# skithSTMv2.net
KiCad netlist of a schematic drawn in EAGLE
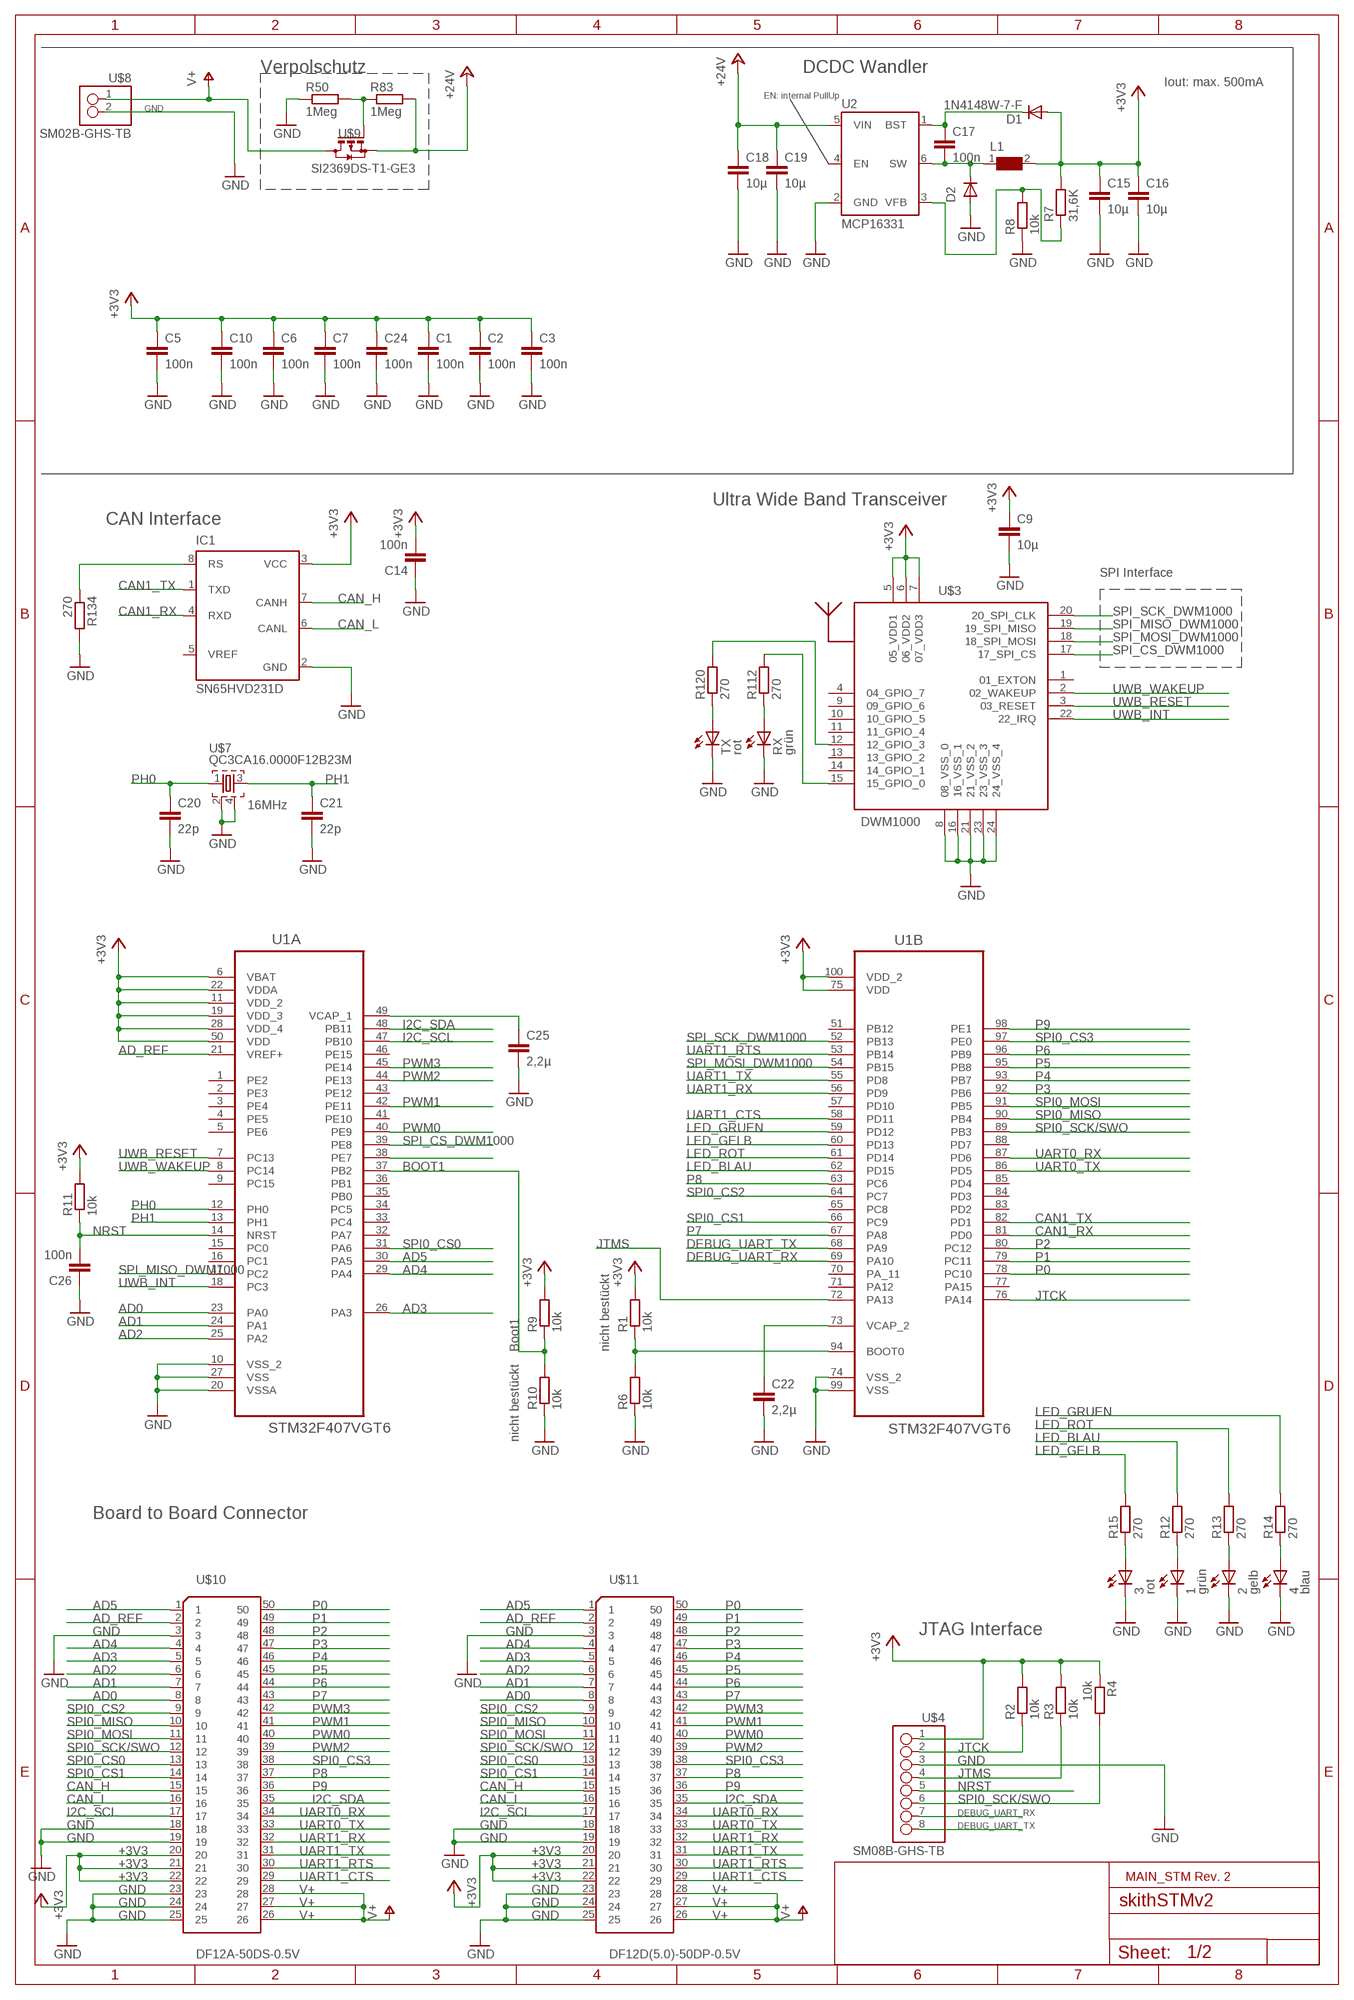
[diagram p0: schematic, sheet 1]
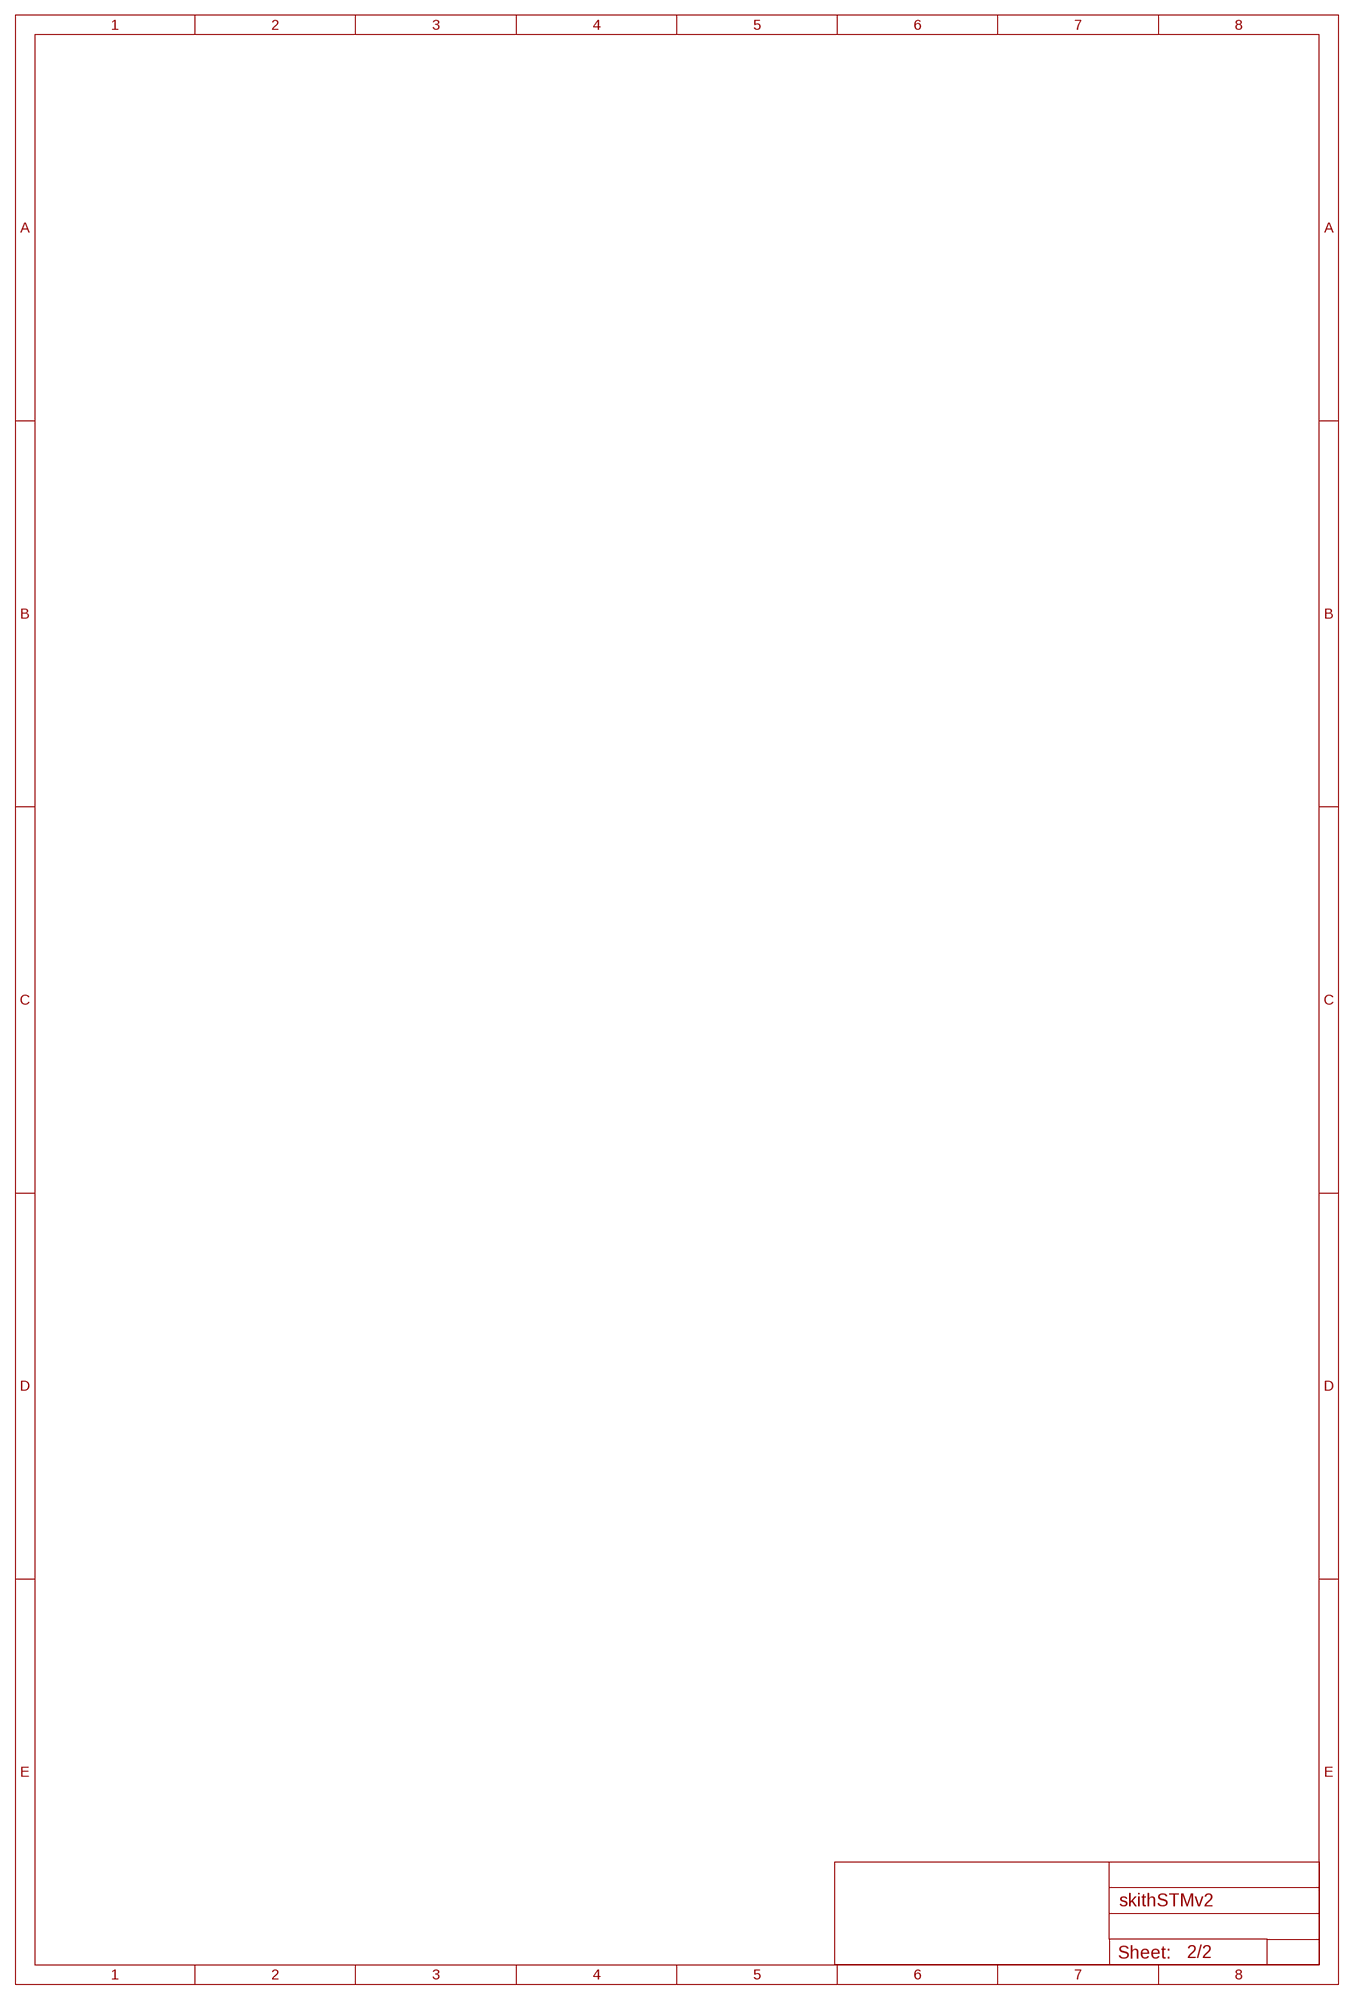
[diagram p1: schematic, sheet 2]

(export (version "E")
  (design (tool "Eeschema 10.0.6"))
  (components
    (comp (ref "1")
      (value "grün")
      (footprint "eagle-import:SML0603")
      (libsource (lib "eagle-import") (part "LEDSML0603"))
    )
    (comp (ref "2")
      (value "gelb")
      (footprint "eagle-import:SML0603")
      (libsource (lib "eagle-import") (part "LEDSML0603"))
    )
    (comp (ref "3")
      (value "rot")
      (footprint "eagle-import:SML0603")
      (libsource (lib "eagle-import") (part "LEDSML0603"))
    )
    (comp (ref "4")
      (value "blau")
      (footprint "eagle-import:SML0603")
      (libsource (lib "eagle-import") (part "LEDSML0603"))
    )
    (comp (ref "C1")
      (value "100n")
      (footprint "eagle-import:C0402")
      (libsource (lib "eagle-import") (part "C-EUC0402"))
    )
    (comp (ref "C2")
      (value "100n")
      (footprint "eagle-import:C0402")
      (libsource (lib "eagle-import") (part "C-EUC0402"))
    )
    (comp (ref "C3")
      (value "100n")
      (footprint "eagle-import:C0402")
      (libsource (lib "eagle-import") (part "C-EUC0402"))
    )
    (comp (ref "C5")
      (value "100n")
      (footprint "eagle-import:C0402")
      (libsource (lib "eagle-import") (part "C-EUC0402"))
    )
    (comp (ref "C6")
      (value "100n")
      (footprint "eagle-import:C0402")
      (libsource (lib "eagle-import") (part "C-EUC0402"))
    )
    (comp (ref "C7")
      (value "100n")
      (footprint "eagle-import:C0402")
      (libsource (lib "eagle-import") (part "C-EUC0402"))
    )
    (comp (ref "C9")
      (value "10µ")
      (footprint "eagle-import:C0805")
      (libsource (lib "eagle-import") (part "C-EUC0805"))
    )
    (comp (ref "C10")
      (value "100n")
      (footprint "eagle-import:C0402")
      (libsource (lib "eagle-import") (part "C-EUC0402"))
    )
    (comp (ref "C14")
      (value "100n")
      (footprint "eagle-import:C0402")
      (libsource (lib "eagle-import") (part "C-EUC0402"))
    )
    (comp (ref "C15")
      (value "10µ")
      (footprint "eagle-import:C0805")
      (libsource (lib "eagle-import") (part "C-EUC0805"))
    )
    (comp (ref "C16")
      (value "10µ")
      (footprint "eagle-import:C0805")
      (libsource (lib "eagle-import") (part "C-EUC0805"))
    )
    (comp (ref "C17")
      (value "100n")
      (footprint "eagle-import:C0402")
      (libsource (lib "eagle-import") (part "C-EUC0402"))
    )
    (comp (ref "C18")
      (value "10µ")
      (footprint "eagle-import:C0805")
      (libsource (lib "eagle-import") (part "C-EUC0805"))
    )
    (comp (ref "C19")
      (value "10µ")
      (footprint "eagle-import:C0805")
      (libsource (lib "eagle-import") (part "C-EUC0805"))
    )
    (comp (ref "C20")
      (value "22p")
      (footprint "eagle-import:C0402")
      (libsource (lib "eagle-import") (part "C-EUC0402"))
    )
    (comp (ref "C21")
      (value "22p")
      (footprint "eagle-import:C0402")
      (libsource (lib "eagle-import") (part "C-EUC0402"))
    )
    (comp (ref "C22")
      (value "2,2µ")
      (footprint "eagle-import:C0402")
      (libsource (lib "eagle-import") (part "C-EUC0402"))
    )
    (comp (ref "C24")
      (value "100n")
      (footprint "eagle-import:C0402")
      (libsource (lib "eagle-import") (part "C-EUC0402"))
    )
    (comp (ref "C25")
      (value "2,2µ")
      (footprint "eagle-import:C0402")
      (libsource (lib "eagle-import") (part "C-EUC0402"))
    )
    (comp (ref "C26")
      (value "100n")
      (footprint "eagle-import:C0402")
      (libsource (lib "eagle-import") (part "C-EUC0402"))
    )
    (comp (ref "D1")
      (value "1N4148W-7-F")
      (footprint "eagle-import:SOD123")
      (libsource (lib "eagle-import") (part "DIODE-SOD123"))
    )
    (comp (ref "D2")
      (value "DIODE-DO214AC")
      (footprint "eagle-import:DO214AC")
      (libsource (lib "eagle-import") (part "DIODE-DO214AC"))
    )
    (comp (ref "IC1")
      (value "SN65HVD231D")
      (footprint "eagle-import:SO8")
      (libsource (lib "eagle-import") (part "PCA82C250T"))
    )
    (comp (ref "L1")
      (value "WE-TPC-744025150_2828")
      (footprint "eagle-import:WE-TPC_2828")
      (fields (field (name "MPN") "744025150"))
      (libsource (lib "eagle-import") (part "WE-TPC_2828-744025150"))
    )
    (comp (ref "R1")
      (value "10k")
      (footprint "eagle-import:R0402")
      (libsource (lib "eagle-import") (part "R-EU_R0402"))
    )
    (comp (ref "R2")
      (value "10k")
      (footprint "eagle-import:R0402")
      (libsource (lib "eagle-import") (part "R-EU_R0402"))
    )
    (comp (ref "R3")
      (value "10k")
      (footprint "eagle-import:R0402")
      (libsource (lib "eagle-import") (part "R-EU_R0402"))
    )
    (comp (ref "R4")
      (value "10k")
      (footprint "eagle-import:R0402")
      (libsource (lib "eagle-import") (part "R-EU_R0402"))
    )
    (comp (ref "R6")
      (value "10k")
      (footprint "eagle-import:R0402")
      (libsource (lib "eagle-import") (part "R-EU_R0402"))
    )
    (comp (ref "R7")
      (value "31,6K")
      (footprint "eagle-import:R0402")
      (libsource (lib "eagle-import") (part "R-EU_R0402"))
    )
    (comp (ref "R8")
      (value "10k")
      (footprint "eagle-import:R0402")
      (libsource (lib "eagle-import") (part "R-EU_R0402"))
    )
    (comp (ref "R9")
      (value "10k")
      (footprint "eagle-import:R0402")
      (libsource (lib "eagle-import") (part "R-EU_R0402"))
    )
    (comp (ref "R10")
      (value "10k")
      (footprint "eagle-import:R0402")
      (libsource (lib "eagle-import") (part "R-EU_R0402"))
    )
    (comp (ref "R11")
      (value "10k")
      (footprint "eagle-import:R0402")
      (libsource (lib "eagle-import") (part "R-EU_R0402"))
    )
    (comp (ref "R12")
      (value "270")
      (footprint "eagle-import:R0402")
      (libsource (lib "eagle-import") (part "R-EU_R0402"))
    )
    (comp (ref "R13")
      (value "270")
      (footprint "eagle-import:R0402")
      (libsource (lib "eagle-import") (part "R-EU_R0402"))
    )
    (comp (ref "R14")
      (value "270")
      (footprint "eagle-import:R0402")
      (libsource (lib "eagle-import") (part "R-EU_R0402"))
    )
    (comp (ref "R15")
      (value "270")
      (footprint "eagle-import:R0402")
      (libsource (lib "eagle-import") (part "R-EU_R0402"))
    )
    (comp (ref "R50")
      (value "1Meg")
      (footprint "eagle-import:R0402")
      (libsource (lib "eagle-import") (part "R-EU_R0402"))
    )
    (comp (ref "R83")
      (value "1Meg")
      (footprint "eagle-import:R0402")
      (libsource (lib "eagle-import") (part "R-EU_R0402"))
    )
    (comp (ref "R112")
      (value "270")
      (footprint "eagle-import:R0402")
      (libsource (lib "eagle-import") (part "R-EU_R0402"))
    )
    (comp (ref "R120")
      (value "270")
      (footprint "eagle-import:R0402")
      (libsource (lib "eagle-import") (part "R-EU_R0402"))
    )
    (comp (ref "R134")
      (value "270")
      (footprint "eagle-import:R0402")
      (libsource (lib "eagle-import") (part "R-EU_R0402"))
    )
    (comp (ref "RX")
      (value "grün")
      (footprint "eagle-import:SML0603")
      (libsource (lib "eagle-import") (part "LEDSML0603"))
    )
    (comp (ref "TX")
      (value "rot")
      (footprint "eagle-import:SML0603")
      (libsource (lib "eagle-import") (part "LEDSML0603"))
    )
    (comp (ref "U$3")
      (value "DWM1000")
      (footprint "eagle-import:DWM1000")
      (libsource (lib "eagle-import") (part "DWM1000"))
    )
    (comp (ref "U$4")
      (value "SM08B-GHS-TB")
      (footprint "eagle-import:SM08B-GHS-TB")
      (libsource (lib "eagle-import") (part "SM08B-GHS-TB"))
    )
    (comp (ref "U$7")
      (value "QC3CA16.0000F12B23M")
      (footprint "eagle-import:LFXTAL055998")
      (libsource (lib "eagle-import") (part "QC3CA12.0000F12B23M"))
    )
    (comp (ref "U$8")
      (value "SM02B-GHS-TB")
      (footprint "eagle-import:SM02B-GHS-TB")
      (libsource (lib "eagle-import") (part "SM02B-GHS-TB"))
    )
    (comp (ref "U$9")
      (value "SI2369DS-T1-GE3")
      (footprint "eagle-import:SOT23")
      (libsource (lib "eagle-import") (part "SI2369DS-T1-GE3"))
    )
    (comp (ref "U$10")
      (value "DF12A-50DS-0.5V")
      (footprint "eagle-import:DF12A-50DS-0.5V")
      (libsource (lib "eagle-import") (part "DF12A-50DS-0.5V"))
    )
    (comp (ref "U$11")
      (value "DF12D(5.0)-50DP-0.5V")
      (footprint "eagle-import:DF12D(5.0)-50DP-0.5V")
      (libsource (lib "eagle-import") (part "DF12D(5.0)-50DP-0.5V"))
    )
    (comp (ref "U1")
      (value "STM32F407VGT6")
      (footprint "eagle-import:QFP50P1600X1600X160-100N")
      (libsource (lib "eagle-import") (part "STM32F407VGT6"))
    )
    (comp (ref "U2")
      (value "MCP16331")
      (footprint "eagle-import:SOT23-6")
      (libsource (lib "eagle-import") (part "MCP16331"))
    )
  )
  (nets
    (net (code "1") (name "+3V3") (class "Default")
      (node (ref "C1") (pin "1") (pinfunction "1_1") (pintype "passive"))
      (node (ref "C10") (pin "1") (pinfunction "1_1") (pintype "passive"))
      (node (ref "C14") (pin "2") (pinfunction "2_2") (pintype "passive"))
      (node (ref "C15") (pin "1") (pinfunction "1_1") (pintype "passive"))
      (node (ref "C16") (pin "1") (pinfunction "1_1") (pintype "passive"))
      (node (ref "C2") (pin "1") (pinfunction "1_1") (pintype "passive"))
      (node (ref "C24") (pin "1") (pinfunction "1_1") (pintype "passive"))
      (node (ref "C3") (pin "1") (pinfunction "1_1") (pintype "passive"))
      (node (ref "C5") (pin "1") (pinfunction "1_1") (pintype "passive"))
      (node (ref "C6") (pin "1") (pinfunction "1_1") (pintype "passive"))
      (node (ref "C7") (pin "1") (pinfunction "1_1") (pintype "passive"))
      (node (ref "C9") (pin "1") (pinfunction "1_1") (pintype "passive"))
      (node (ref "D1") (pin "A") (pinfunction "A_A") (pintype "passive"))
      (node (ref "IC1") (pin "3") (pinfunction "VCC_3") (pintype "power_in"))
      (node (ref "L1") (pin "2") (pinfunction "2_2") (pintype "passive"))
      (node (ref "R1") (pin "2") (pinfunction "2_2") (pintype "passive"))
      (node (ref "R11") (pin "2") (pinfunction "2_2") (pintype "passive"))
      (node (ref "R2") (pin "2") (pinfunction "2_2") (pintype "passive"))
      (node (ref "R3") (pin "2") (pinfunction "2_2") (pintype "passive"))
      (node (ref "R4") (pin "1") (pinfunction "1_1") (pintype "passive"))
      (node (ref "R7") (pin "2") (pinfunction "2_2") (pintype "passive"))
      (node (ref "R9") (pin "2") (pinfunction "2_2") (pintype "passive"))
      (node (ref "U$10") (pin "20") (pinfunction "20_20") (pintype "bidirectional"))
      (node (ref "U$10") (pin "21") (pinfunction "21_21") (pintype "bidirectional"))
      (node (ref "U$10") (pin "22") (pinfunction "22_22") (pintype "bidirectional"))
      (node (ref "U$11") (pin "20") (pinfunction "20_20") (pintype "bidirectional"))
      (node (ref "U$11") (pin "21") (pinfunction "21_21") (pintype "bidirectional"))
      (node (ref "U$11") (pin "22") (pinfunction "22_22") (pintype "bidirectional"))
      (node (ref "U$3") (pin "5") (pinfunction "05_VDD1_5") (pintype "bidirectional"))
      (node (ref "U$3") (pin "6") (pinfunction "06_VDD2_6") (pintype "bidirectional"))
      (node (ref "U$3") (pin "7") (pinfunction "07_VDD3_7") (pintype "bidirectional"))
      (node (ref "U$4") (pin "1") (pinfunction "P$1_1") (pintype "bidirectional"))
      (node (ref "U1") (pin "100") (pinfunction "VDD_2_100") (pintype "power_in"))
      (node (ref "U1") (pin "11") (pinfunction "VDD_2_11") (pintype "power_in"))
      (node (ref "U1") (pin "19") (pinfunction "VDD_3_19") (pintype "power_in"))
      (node (ref "U1") (pin "22") (pinfunction "VDDA_22") (pintype "power_in"))
      (node (ref "U1") (pin "28") (pinfunction "VDD_4_28") (pintype "power_in"))
      (node (ref "U1") (pin "50") (pinfunction "VDD_50") (pintype "power_in"))
      (node (ref "U1") (pin "6") (pinfunction "VBAT_6") (pintype "power_in"))
      (node (ref "U1") (pin "75") (pinfunction "VDD_75") (pintype "power_in"))
    )
    (net (code "2") (name "+24V") (class "Default")
      (node (ref "C18") (pin "1") (pinfunction "1_1") (pintype "passive"))
      (node (ref "C19") (pin "1") (pinfunction "1_1") (pintype "passive"))
      (node (ref "R83") (pin "2") (pinfunction "2_2") (pintype "passive"))
      (node (ref "U$9") (pin "2") (pinfunction "S_2") (pintype "passive"))
      (node (ref "U2") (pin "5") (pinfunction "VIN_5") (pintype "bidirectional"))
    )
    (net (code "3") (name "AD0") (class "Default")
      (node (ref "U$10") (pin "8") (pinfunction "8_8") (pintype "bidirectional"))
      (node (ref "U$11") (pin "8") (pinfunction "8_8") (pintype "bidirectional"))
      (node (ref "U1") (pin "23") (pinfunction "PA0_23") (pintype "bidirectional"))
    )
    (net (code "4") (name "AD1") (class "Default")
      (node (ref "U$10") (pin "7") (pinfunction "7_7") (pintype "bidirectional"))
      (node (ref "U$11") (pin "7") (pinfunction "7_7") (pintype "bidirectional"))
      (node (ref "U1") (pin "24") (pinfunction "PA1_24") (pintype "bidirectional"))
    )
    (net (code "5") (name "AD2") (class "Default")
      (node (ref "U$10") (pin "6") (pinfunction "6_6") (pintype "bidirectional"))
      (node (ref "U$11") (pin "6") (pinfunction "6_6") (pintype "bidirectional"))
      (node (ref "U1") (pin "25") (pinfunction "PA2_25") (pintype "bidirectional"))
    )
    (net (code "6") (name "AD3") (class "Default")
      (node (ref "U$10") (pin "5") (pinfunction "5_5") (pintype "bidirectional"))
      (node (ref "U$11") (pin "5") (pinfunction "5_5") (pintype "bidirectional"))
      (node (ref "U1") (pin "26") (pinfunction "PA3_26") (pintype "bidirectional"))
    )
    (net (code "7") (name "AD4") (class "Default")
      (node (ref "U$10") (pin "4") (pinfunction "4_4") (pintype "bidirectional"))
      (node (ref "U$11") (pin "4") (pinfunction "4_4") (pintype "bidirectional"))
      (node (ref "U1") (pin "29") (pinfunction "PA4_29") (pintype "bidirectional"))
    )
    (net (code "8") (name "AD5") (class "Default")
      (node (ref "U$10") (pin "1") (pinfunction "1_1") (pintype "bidirectional"))
      (node (ref "U$11") (pin "1") (pinfunction "1_1") (pintype "bidirectional"))
      (node (ref "U1") (pin "30") (pinfunction "PA5_30") (pintype "bidirectional"))
    )
    (net (code "9") (name "AD_REF") (class "Default")
      (node (ref "U$10") (pin "2") (pinfunction "2_2") (pintype "bidirectional"))
      (node (ref "U$11") (pin "2") (pinfunction "2_2") (pintype "bidirectional"))
      (node (ref "U1") (pin "21") (pinfunction "VREF+_21") (pintype "power_in"))
    )
    (net (code "10") (name "BOOT1") (class "Default")
      (node (ref "R10") (pin "2") (pinfunction "2_2") (pintype "passive"))
      (node (ref "R9") (pin "1") (pinfunction "1_1") (pintype "passive"))
      (node (ref "U1") (pin "37") (pinfunction "PB2_37") (pintype "bidirectional"))
    )
    (net (code "11") (name "CAN1_RX") (class "Default")
      (node (ref "IC1") (pin "4") (pinfunction "RXD_4") (pintype "output"))
      (node (ref "U1") (pin "81") (pinfunction "PD0_81") (pintype "bidirectional"))
    )
    (net (code "12") (name "CAN1_TX") (class "Default")
      (node (ref "IC1") (pin "1") (pinfunction "TXD_1") (pintype "input"))
      (node (ref "U1") (pin "82") (pinfunction "PD1_82") (pintype "bidirectional"))
    )
    (net (code "13") (name "CAN_H") (class "Default")
      (node (ref "IC1") (pin "7") (pinfunction "CANH_7") (pintype "bidirectional"))
      (node (ref "U$10") (pin "15") (pinfunction "15_15") (pintype "bidirectional"))
      (node (ref "U$11") (pin "15") (pinfunction "15_15") (pintype "bidirectional"))
    )
    (net (code "14") (name "CAN_L") (class "Default")
      (node (ref "IC1") (pin "6") (pinfunction "CANL_6") (pintype "bidirectional"))
      (node (ref "U$10") (pin "16") (pinfunction "16_16") (pintype "bidirectional"))
      (node (ref "U$11") (pin "16") (pinfunction "16_16") (pintype "bidirectional"))
    )
    (net (code "15") (name "DEBUG_UART_RX") (class "Default")
      (node (ref "U$4") (pin "7") (pinfunction "P$7_7") (pintype "bidirectional"))
      (node (ref "U1") (pin "69") (pinfunction "PA10_69") (pintype "bidirectional"))
    )
    (net (code "16") (name "DEBUG_UART_TX") (class "Default")
      (node (ref "U$4") (pin "8") (pinfunction "P$8_8") (pintype "bidirectional"))
      (node (ref "U1") (pin "68") (pinfunction "PA9_68") (pintype "bidirectional"))
    )
    (net (code "17") (name "GND") (class "Default")
      (node (ref "1") (pin "C") (pinfunction "C_C") (pintype "passive"))
      (node (ref "2") (pin "C") (pinfunction "C_C") (pintype "passive"))
      (node (ref "3") (pin "C") (pinfunction "C_C") (pintype "passive"))
      (node (ref "4") (pin "C") (pinfunction "C_C") (pintype "passive"))
      (node (ref "C1") (pin "2") (pinfunction "2_2") (pintype "passive"))
      (node (ref "C10") (pin "2") (pinfunction "2_2") (pintype "passive"))
      (node (ref "C14") (pin "1") (pinfunction "1_1") (pintype "passive"))
      (node (ref "C15") (pin "2") (pinfunction "2_2") (pintype "passive"))
      (node (ref "C16") (pin "2") (pinfunction "2_2") (pintype "passive"))
      (node (ref "C18") (pin "2") (pinfunction "2_2") (pintype "passive"))
      (node (ref "C19") (pin "2") (pinfunction "2_2") (pintype "passive"))
      (node (ref "C2") (pin "2") (pinfunction "2_2") (pintype "passive"))
      (node (ref "C20") (pin "2") (pinfunction "2_2") (pintype "passive"))
      (node (ref "C21") (pin "2") (pinfunction "2_2") (pintype "passive"))
      (node (ref "C22") (pin "2") (pinfunction "2_2") (pintype "passive"))
      (node (ref "C24") (pin "2") (pinfunction "2_2") (pintype "passive"))
      (node (ref "C25") (pin "2") (pinfunction "2_2") (pintype "passive"))
      (node (ref "C26") (pin "1") (pinfunction "1_1") (pintype "passive"))
      (node (ref "C3") (pin "2") (pinfunction "2_2") (pintype "passive"))
      (node (ref "C5") (pin "2") (pinfunction "2_2") (pintype "passive"))
      (node (ref "C6") (pin "2") (pinfunction "2_2") (pintype "passive"))
      (node (ref "C7") (pin "2") (pinfunction "2_2") (pintype "passive"))
      (node (ref "C9") (pin "2") (pinfunction "2_2") (pintype "passive"))
      (node (ref "D2") (pin "A") (pinfunction "A_A") (pintype "passive"))
      (node (ref "IC1") (pin "2") (pinfunction "GND_2") (pintype "power_in"))
      (node (ref "R10") (pin "1") (pinfunction "1_1") (pintype "passive"))
      (node (ref "R134") (pin "2") (pinfunction "2_2") (pintype "passive"))
      (node (ref "R50") (pin "1") (pinfunction "1_1") (pintype "passive"))
      (node (ref "R6") (pin "1") (pinfunction "1_1") (pintype "passive"))
      (node (ref "R8") (pin "1") (pinfunction "1_1") (pintype "passive"))
      (node (ref "RX") (pin "C") (pinfunction "C_C") (pintype "passive"))
      (node (ref "TX") (pin "C") (pinfunction "C_C") (pintype "passive"))
      (node (ref "U$10") (pin "18") (pinfunction "18_18") (pintype "bidirectional"))
      (node (ref "U$10") (pin "19") (pinfunction "19_19") (pintype "bidirectional"))
      (node (ref "U$10") (pin "23") (pinfunction "23_23") (pintype "bidirectional"))
      (node (ref "U$10") (pin "24") (pinfunction "24_24") (pintype "bidirectional"))
      (node (ref "U$10") (pin "25") (pinfunction "25_25") (pintype "bidirectional"))
      (node (ref "U$10") (pin "3") (pinfunction "3_3") (pintype "bidirectional"))
      (node (ref "U$11") (pin "18") (pinfunction "18_18") (pintype "bidirectional"))
      (node (ref "U$11") (pin "19") (pinfunction "19_19") (pintype "bidirectional"))
      (node (ref "U$11") (pin "23") (pinfunction "23_23") (pintype "bidirectional"))
      (node (ref "U$11") (pin "24") (pinfunction "24_24") (pintype "bidirectional"))
      (node (ref "U$11") (pin "25") (pinfunction "25_25") (pintype "bidirectional"))
      (node (ref "U$11") (pin "3") (pinfunction "3_3") (pintype "bidirectional"))
      (node (ref "U$3") (pin "16") (pinfunction "16_VSS_1_16") (pintype "bidirectional"))
      (node (ref "U$3") (pin "21") (pinfunction "21_VSS_2_21") (pintype "bidirectional"))
      (node (ref "U$3") (pin "23") (pinfunction "23_VSS_3_23") (pintype "bidirectional"))
      (node (ref "U$3") (pin "24") (pinfunction "24_VSS_4_24") (pintype "bidirectional"))
      (node (ref "U$3") (pin "8") (pinfunction "08_VSS_0_8") (pintype "bidirectional"))
      (node (ref "U$4") (pin "3") (pinfunction "P$3_3") (pintype "bidirectional"))
      (node (ref "U$7") (pin "2") (pinfunction "2_2") (pintype "passive"))
      (node (ref "U$7") (pin "4") (pinfunction "4_4") (pintype "passive"))
      (node (ref "U$8") (pin "2") (pinfunction "P$2_2") (pintype "bidirectional"))
      (node (ref "U1") (pin "10") (pinfunction "VSS_2_10") (pintype "passive"))
      (node (ref "U1") (pin "20") (pinfunction "VSSA_20") (pintype "passive"))
      (node (ref "U1") (pin "27") (pinfunction "VSS_27") (pintype "passive"))
      (node (ref "U1") (pin "74") (pinfunction "VSS_2_74") (pintype "passive"))
      (node (ref "U1") (pin "99") (pinfunction "VSS_99") (pintype "passive"))
      (node (ref "U2") (pin "2") (pinfunction "GND_2") (pintype "bidirectional"))
    )
    (net (code "18") (name "I2C_SCL") (class "Default")
      (node (ref "U$10") (pin "17") (pinfunction "17_17") (pintype "bidirectional"))
      (node (ref "U$11") (pin "17") (pinfunction "17_17") (pintype "bidirectional"))
      (node (ref "U1") (pin "47") (pinfunction "PB10_47") (pintype "bidirectional"))
    )
    (net (code "19") (name "I2C_SDA") (class "Default")
      (node (ref "U$10") (pin "35") (pinfunction "35_35") (pintype "bidirectional"))
      (node (ref "U$11") (pin "35") (pinfunction "35_35") (pintype "bidirectional"))
      (node (ref "U1") (pin "48") (pinfunction "PB11_48") (pintype "bidirectional"))
    )
    (net (code "20") (name "JTCK") (class "Default")
      (node (ref "R2") (pin "1") (pinfunction "1_1") (pintype "passive"))
      (node (ref "U$4") (pin "2") (pinfunction "P$2_2") (pintype "bidirectional"))
      (node (ref "U1") (pin "76") (pinfunction "PA14_76") (pintype "bidirectional"))
    )
    (net (code "21") (name "JTMS") (class "Default")
      (node (ref "R3") (pin "1") (pinfunction "1_1") (pintype "passive"))
      (node (ref "U$4") (pin "4") (pinfunction "P$4_4") (pintype "bidirectional"))
      (node (ref "U1") (pin "72") (pinfunction "PA13_72") (pintype "bidirectional"))
    )
    (net (code "22") (name "LED_BLAU") (class "Default")
      (node (ref "R12") (pin "2") (pinfunction "2_2") (pintype "passive"))
      (node (ref "U1") (pin "62") (pinfunction "PD15_62") (pintype "bidirectional"))
    )
    (net (code "23") (name "LED_GELB") (class "Default")
      (node (ref "R15") (pin "2") (pinfunction "2_2") (pintype "passive"))
      (node (ref "U1") (pin "60") (pinfunction "PD13_60") (pintype "bidirectional"))
    )
    (net (code "24") (name "LED_GRUEN") (class "Default")
      (node (ref "R14") (pin "2") (pinfunction "2_2") (pintype "passive"))
      (node (ref "U1") (pin "59") (pinfunction "PD12_59") (pintype "bidirectional"))
    )
    (net (code "25") (name "LED_ROT") (class "Default")
      (node (ref "R13") (pin "2") (pinfunction "2_2") (pintype "passive"))
      (node (ref "U1") (pin "61") (pinfunction "PD14_61") (pintype "bidirectional"))
    )
    (net (code "26") (name "NRST") (class "Default")
      (node (ref "C26") (pin "2") (pinfunction "2_2") (pintype "passive"))
      (node (ref "R11") (pin "1") (pinfunction "1_1") (pintype "passive"))
      (node (ref "U$4") (pin "5") (pinfunction "P$5_5") (pintype "bidirectional"))
      (node (ref "U1") (pin "14") (pinfunction "NRST_14") (pintype "bidirectional"))
    )
    (net (code "27") (name "Net-(1-PadA)") (class "Default")
      (node (ref "1") (pin "A") (pinfunction "A_A") (pintype "passive"))
      (node (ref "R12") (pin "1") (pinfunction "1_1") (pintype "passive"))
    )
    (net (code "28") (name "Net-(2-PadA)") (class "Default")
      (node (ref "2") (pin "A") (pinfunction "A_A") (pintype "passive"))
      (node (ref "R13") (pin "1") (pinfunction "1_1") (pintype "passive"))
    )
    (net (code "29") (name "Net-(3-PadA)") (class "Default")
      (node (ref "3") (pin "A") (pinfunction "A_A") (pintype "passive"))
      (node (ref "R15") (pin "1") (pinfunction "1_1") (pintype "passive"))
    )
    (net (code "30") (name "Net-(4-PadA)") (class "Default")
      (node (ref "4") (pin "A") (pinfunction "A_A") (pintype "passive"))
      (node (ref "R14") (pin "1") (pinfunction "1_1") (pintype "passive"))
    )
    (net (code "31") (name "Net-(IC1-RS)") (class "Default")
      (node (ref "IC1") (pin "8") (pinfunction "RS_8") (pintype "input"))
      (node (ref "R134") (pin "1") (pinfunction "1_1") (pintype "passive"))
    )
    (net (code "32") (name "Net-(R112-Pad1)") (class "Default")
      (node (ref "R112") (pin "1") (pinfunction "1_1") (pintype "passive"))
      (node (ref "RX") (pin "A") (pinfunction "A_A") (pintype "passive"))
    )
    (net (code "33") (name "Net-(R120-Pad1)") (class "Default")
      (node (ref "R120") (pin "1") (pinfunction "1_1") (pintype "passive"))
      (node (ref "TX") (pin "A") (pinfunction "A_A") (pintype "passive"))
    )
    (net (code "34") (name "Net-(U$3-12_GPIO_3)") (class "Default")
      (node (ref "R120") (pin "2") (pinfunction "2_2") (pintype "passive"))
      (node (ref "U$3") (pin "12") (pinfunction "12_GPIO_3_12") (pintype "bidirectional"))
    )
    (net (code "35") (name "Net-(U$3-15_GPIO_0)") (class "Default")
      (node (ref "R112") (pin "2") (pinfunction "2_2") (pintype "passive"))
      (node (ref "U$3") (pin "15") (pinfunction "15_GPIO_0_15") (pintype "bidirectional"))
    )
    (net (code "36") (name "Net-(U$9-G)") (class "Default")
      (node (ref "R50") (pin "2") (pinfunction "2_2") (pintype "passive"))
      (node (ref "R83") (pin "1") (pinfunction "1_1") (pintype "passive"))
      (node (ref "U$9") (pin "1") (pinfunction "G_1") (pintype "passive"))
    )
    (net (code "37") (name "Net-(U1A-VCAP_1)") (class "Default")
      (node (ref "C25") (pin "1") (pinfunction "1_1") (pintype "passive"))
      (node (ref "U1") (pin "49") (pinfunction "VCAP_1_49") (pintype "power_in"))
    )
    (net (code "38") (name "Net-(U1B-BOOT0)") (class "Default")
      (node (ref "R1") (pin "1") (pinfunction "1_1") (pintype "passive"))
      (node (ref "R6") (pin "2") (pinfunction "2_2") (pintype "passive"))
      (node (ref "U1") (pin "94") (pinfunction "BOOT0_94") (pintype "input"))
    )
    (net (code "39") (name "Net-(U1B-VCAP_2)") (class "Default")
      (node (ref "C22") (pin "1") (pinfunction "1_1") (pintype "passive"))
      (node (ref "U1") (pin "73") (pinfunction "VCAP_2_73") (pintype "power_in"))
    )
    (net (code "40") (name "Net-(U2-BST)") (class "Default")
      (node (ref "C17") (pin "1") (pinfunction "1_1") (pintype "passive"))
      (node (ref "D1") (pin "C") (pinfunction "C_C") (pintype "passive"))
      (node (ref "U2") (pin "1") (pinfunction "BST_1") (pintype "bidirectional"))
    )
    (net (code "41") (name "Net-(U2-SW)") (class "Default")
      (node (ref "C17") (pin "2") (pinfunction "2_2") (pintype "passive"))
      (node (ref "D2") (pin "C") (pinfunction "C_C") (pintype "passive"))
      (node (ref "L1") (pin "1") (pinfunction "1_1") (pintype "passive"))
      (node (ref "U2") (pin "6") (pinfunction "SW_6") (pintype "bidirectional"))
    )
    (net (code "42") (name "Net-(U2-VFB)") (class "Default")
      (node (ref "R7") (pin "1") (pinfunction "1_1") (pintype "passive"))
      (node (ref "R8") (pin "2") (pinfunction "2_2") (pintype "passive"))
      (node (ref "U2") (pin "3") (pinfunction "VFB_3") (pintype "bidirectional"))
    )
    (net (code "43") (name "P0") (class "Default")
      (node (ref "U$10") (pin "50") (pinfunction "50_50") (pintype "bidirectional"))
      (node (ref "U$11") (pin "50") (pinfunction "50_50") (pintype "bidirectional"))
      (node (ref "U1") (pin "78") (pinfunction "PC10_78") (pintype "bidirectional"))
    )
    (net (code "44") (name "P1") (class "Default")
      (node (ref "U$10") (pin "49") (pinfunction "49_49") (pintype "bidirectional"))
      (node (ref "U$11") (pin "49") (pinfunction "49_49") (pintype "bidirectional"))
      (node (ref "U1") (pin "79") (pinfunction "PC11_79") (pintype "bidirectional"))
    )
    (net (code "45") (name "P2") (class "Default")
      (node (ref "U$10") (pin "48") (pinfunction "48_48") (pintype "bidirectional"))
      (node (ref "U$11") (pin "48") (pinfunction "48_48") (pintype "bidirectional"))
      (node (ref "U1") (pin "80") (pinfunction "PC12_80") (pintype "bidirectional"))
    )
    (net (code "46") (name "P3") (class "Default")
      (node (ref "U$10") (pin "47") (pinfunction "47_47") (pintype "bidirectional"))
      (node (ref "U$11") (pin "47") (pinfunction "47_47") (pintype "bidirectional"))
      (node (ref "U1") (pin "92") (pinfunction "PB6_92") (pintype "bidirectional"))
    )
    (net (code "47") (name "P4") (class "Default")
      (node (ref "U$10") (pin "46") (pinfunction "46_46") (pintype "bidirectional"))
      (node (ref "U$11") (pin "46") (pinfunction "46_46") (pintype "bidirectional"))
      (node (ref "U1") (pin "93") (pinfunction "PB7_93") (pintype "bidirectional"))
    )
    (net (code "48") (name "P5") (class "Default")
      (node (ref "U$10") (pin "45") (pinfunction "45_45") (pintype "bidirectional"))
      (node (ref "U$11") (pin "45") (pinfunction "45_45") (pintype "bidirectional"))
      (node (ref "U1") (pin "95") (pinfunction "PB8_95") (pintype "bidirectional"))
    )
    (net (code "49") (name "P6") (class "Default")
      (node (ref "U$10") (pin "44") (pinfunction "44_44") (pintype "bidirectional"))
      (node (ref "U$11") (pin "44") (pinfunction "44_44") (pintype "bidirectional"))
      (node (ref "U1") (pin "96") (pinfunction "PB9_96") (pintype "bidirectional"))
    )
    (net (code "50") (name "P7") (class "Default")
      (node (ref "U$10") (pin "43") (pinfunction "43_43") (pintype "bidirectional"))
      (node (ref "U$11") (pin "43") (pinfunction "43_43") (pintype "bidirectional"))
      (node (ref "U1") (pin "67") (pinfunction "PA8_67") (pintype "bidirectional"))
    )
    (net (code "51") (name "P8") (class "Default")
      (node (ref "U$10") (pin "37") (pinfunction "37_37") (pintype "bidirectional"))
      (node (ref "U$11") (pin "37") (pinfunction "37_37") (pintype "bidirectional"))
      (node (ref "U1") (pin "63") (pinfunction "PC6_63") (pintype "bidirectional"))
    )
    (net (code "52") (name "P9") (class "Default")
      (node (ref "U$10") (pin "36") (pinfunction "36_36") (pintype "bidirectional"))
      (node (ref "U$11") (pin "36") (pinfunction "36_36") (pintype "bidirectional"))
      (node (ref "U1") (pin "98") (pinfunction "PE1_98") (pintype "bidirectional"))
    )
    (net (code "53") (name "PH0") (class "Default")
      (node (ref "C20") (pin "1") (pinfunction "1_1") (pintype "passive"))
      (node (ref "U$7") (pin "1") (pinfunction "1_1") (pintype "passive"))
      (node (ref "U1") (pin "12") (pinfunction "PH0_12") (pintype "bidirectional"))
    )
    (net (code "54") (name "PH1") (class "Default")
      (node (ref "C21") (pin "1") (pinfunction "1_1") (pintype "passive"))
      (node (ref "U$7") (pin "3") (pinfunction "3_3") (pintype "passive"))
      (node (ref "U1") (pin "13") (pinfunction "PH1_13") (pintype "bidirectional"))
    )
    (net (code "55") (name "PWM0") (class "Default")
      (node (ref "U$10") (pin "40") (pinfunction "40_40") (pintype "bidirectional"))
      (node (ref "U$11") (pin "40") (pinfunction "40_40") (pintype "bidirectional"))
      (node (ref "U1") (pin "40") (pinfunction "PE9_40") (pintype "bidirectional"))
    )
    (net (code "56") (name "PWM1") (class "Default")
      (node (ref "U$10") (pin "41") (pinfunction "41_41") (pintype "bidirectional"))
      (node (ref "U$11") (pin "41") (pinfunction "41_41") (pintype "bidirectional"))
      (node (ref "U1") (pin "42") (pinfunction "PE11_42") (pintype "bidirectional"))
    )
    (net (code "57") (name "PWM2") (class "Default")
      (node (ref "U$10") (pin "39") (pinfunction "39_39") (pintype "bidirectional"))
      (node (ref "U$11") (pin "39") (pinfunction "39_39") (pintype "bidirectional"))
      (node (ref "U1") (pin "44") (pinfunction "PE13_44") (pintype "bidirectional"))
    )
    (net (code "58") (name "PWM3") (class "Default")
      (node (ref "U$10") (pin "42") (pinfunction "42_42") (pintype "bidirectional"))
      (node (ref "U$11") (pin "42") (pinfunction "42_42") (pintype "bidirectional"))
      (node (ref "U1") (pin "45") (pinfunction "PE14_45") (pintype "bidirectional"))
    )
    (net (code "59") (name "SPI0_CS0") (class "Default")
      (node (ref "U$10") (pin "13") (pinfunction "13_13") (pintype "bidirectional"))
      (node (ref "U$11") (pin "13") (pinfunction "13_13") (pintype "bidirectional"))
      (node (ref "U1") (pin "31") (pinfunction "PA6_31") (pintype "bidirectional"))
    )
    (net (code "60") (name "SPI0_CS1") (class "Default")
      (node (ref "U$10") (pin "14") (pinfunction "14_14") (pintype "bidirectional"))
      (node (ref "U$11") (pin "14") (pinfunction "14_14") (pintype "bidirectional"))
      (node (ref "U1") (pin "66") (pinfunction "PC9_66") (pintype "bidirectional"))
    )
    (net (code "61") (name "SPI0_CS2") (class "Default")
      (node (ref "U$10") (pin "9") (pinfunction "9_9") (pintype "bidirectional"))
      (node (ref "U$11") (pin "9") (pinfunction "9_9") (pintype "bidirectional"))
      (node (ref "U1") (pin "64") (pinfunction "PC7_64") (pintype "bidirectional"))
    )
    (net (code "62") (name "SPI0_CS3") (class "Default")
      (node (ref "U$10") (pin "38") (pinfunction "38_38") (pintype "bidirectional"))
      (node (ref "U$11") (pin "38") (pinfunction "38_38") (pintype "bidirectional"))
      (node (ref "U1") (pin "97") (pinfunction "PE0_97") (pintype "bidirectional"))
    )
    (net (code "63") (name "SPI0_MISO") (class "Default")
      (node (ref "U$10") (pin "10") (pinfunction "10_10") (pintype "bidirectional"))
      (node (ref "U$11") (pin "10") (pinfunction "10_10") (pintype "bidirectional"))
      (node (ref "U1") (pin "90") (pinfunction "PB4_90") (pintype "bidirectional"))
    )
    (net (code "64") (name "SPI0_MOSI") (class "Default")
      (node (ref "U$10") (pin "11") (pinfunction "11_11") (pintype "bidirectional"))
      (node (ref "U$11") (pin "11") (pinfunction "11_11") (pintype "bidirectional"))
      (node (ref "U1") (pin "91") (pinfunction "PB5_91") (pintype "bidirectional"))
    )
    (net (code "65") (name "SPI0_SCK{slash}SWO") (class "Default")
      (node (ref "R4") (pin "2") (pinfunction "2_2") (pintype "passive"))
      (node (ref "U$10") (pin "12") (pinfunction "12_12") (pintype "bidirectional"))
      (node (ref "U$11") (pin "12") (pinfunction "12_12") (pintype "bidirectional"))
      (node (ref "U$4") (pin "6") (pinfunction "P$6_6") (pintype "bidirectional"))
      (node (ref "U1") (pin "89") (pinfunction "PB3_89") (pintype "bidirectional"))
    )
    (net (code "66") (name "SPI_CS_DWM1000") (class "Default")
      (node (ref "U$3") (pin "17") (pinfunction "17_SPI_CS_17") (pintype "bidirectional"))
      (node (ref "U1") (pin "39") (pinfunction "PE8_39") (pintype "bidirectional"))
    )
    (net (code "67") (name "SPI_MISO_DWM1000") (class "Default")
      (node (ref "U$3") (pin "19") (pinfunction "19_SPI_MISO_19") (pintype "bidirectional"))
      (node (ref "U1") (pin "17") (pinfunction "PC2_17") (pintype "bidirectional"))
    )
    (net (code "68") (name "SPI_MOSI_DWM1000") (class "Default")
      (node (ref "U$3") (pin "18") (pinfunction "18_SPI_MOSI_18") (pintype "bidirectional"))
      (node (ref "U1") (pin "54") (pinfunction "PB15_54") (pintype "bidirectional"))
    )
    (net (code "69") (name "SPI_SCK_DWM1000") (class "Default")
      (node (ref "U$3") (pin "20") (pinfunction "20_SPI_CLK_20") (pintype "bidirectional"))
      (node (ref "U1") (pin "52") (pinfunction "PB13_52") (pintype "bidirectional"))
    )
    (net (code "70") (name "UART0_RX") (class "Default")
      (node (ref "U$10") (pin "34") (pinfunction "34_34") (pintype "bidirectional"))
      (node (ref "U$11") (pin "34") (pinfunction "34_34") (pintype "bidirectional"))
      (node (ref "U1") (pin "87") (pinfunction "PD6_87") (pintype "bidirectional"))
    )
    (net (code "71") (name "UART0_TX") (class "Default")
      (node (ref "U$10") (pin "33") (pinfunction "33_33") (pintype "bidirectional"))
      (node (ref "U$11") (pin "33") (pinfunction "33_33") (pintype "bidirectional"))
      (node (ref "U1") (pin "86") (pinfunction "PD5_86") (pintype "bidirectional"))
    )
    (net (code "72") (name "UART1_CTS") (class "Default")
      (node (ref "U$10") (pin "29") (pinfunction "29_29") (pintype "bidirectional"))
      (node (ref "U$11") (pin "29") (pinfunction "29_29") (pintype "bidirectional"))
      (node (ref "U1") (pin "58") (pinfunction "PD11_58") (pintype "bidirectional"))
    )
    (net (code "73") (name "UART1_RTS") (class "Default")
      (node (ref "U$10") (pin "30") (pinfunction "30_30") (pintype "bidirectional"))
      (node (ref "U$11") (pin "30") (pinfunction "30_30") (pintype "bidirectional"))
      (node (ref "U1") (pin "53") (pinfunction "PB14_53") (pintype "bidirectional"))
    )
    (net (code "74") (name "UART1_RX") (class "Default")
      (node (ref "U$10") (pin "32") (pinfunction "32_32") (pintype "bidirectional"))
      (node (ref "U$11") (pin "32") (pinfunction "32_32") (pintype "bidirectional"))
      (node (ref "U1") (pin "56") (pinfunction "PD9_56") (pintype "bidirectional"))
    )
    (net (code "75") (name "UART1_TX") (class "Default")
      (node (ref "U$10") (pin "31") (pinfunction "31_31") (pintype "bidirectional"))
      (node (ref "U$11") (pin "31") (pinfunction "31_31") (pintype "bidirectional"))
      (node (ref "U1") (pin "55") (pinfunction "PD8_55") (pintype "bidirectional"))
    )
    (net (code "76") (name "UWB_INT") (class "Default")
      (node (ref "U$3") (pin "22") (pinfunction "22_IRQ_22") (pintype "bidirectional"))
      (node (ref "U1") (pin "18") (pinfunction "PC3_18") (pintype "bidirectional"))
    )
    (net (code "77") (name "UWB_RESET") (class "Default")
      (node (ref "U$3") (pin "3") (pinfunction "03_RESET_3") (pintype "bidirectional"))
      (node (ref "U1") (pin "7") (pinfunction "PC13_7") (pintype "bidirectional"))
    )
    (net (code "78") (name "UWB_WAKEUP") (class "Default")
      (node (ref "U$3") (pin "2") (pinfunction "02_WAKEUP_2") (pintype "bidirectional"))
      (node (ref "U1") (pin "8") (pinfunction "PC14_8") (pintype "bidirectional"))
    )
    (net (code "79") (name "V+") (class "Default")
      (node (ref "U$10") (pin "26") (pinfunction "26_26") (pintype "bidirectional"))
      (node (ref "U$10") (pin "27") (pinfunction "27_27") (pintype "bidirectional"))
      (node (ref "U$10") (pin "28") (pinfunction "28_28") (pintype "bidirectional"))
      (node (ref "U$11") (pin "26") (pinfunction "26_26") (pintype "bidirectional"))
      (node (ref "U$11") (pin "27") (pinfunction "27_27") (pintype "bidirectional"))
      (node (ref "U$11") (pin "28") (pinfunction "28_28") (pintype "bidirectional"))
      (node (ref "U$8") (pin "1") (pinfunction "P$1_1") (pintype "bidirectional"))
      (node (ref "U$9") (pin "3") (pinfunction "D_3") (pintype "passive"))
    )
    (net (code "80") (name "unconnected-(IC1-VREF-Pad5)") (class "Default")
      (node (ref "IC1") (pin "5") (pinfunction "VREF_5") (pintype "output"))
    )
    (net (code "81") (name "unconnected-(U$3-01_EXTON-Pad1)") (class "Default")
      (node (ref "U$3") (pin "1") (pinfunction "01_EXTON_1") (pintype "bidirectional"))
    )
    (net (code "82") (name "unconnected-(U$3-04_GPIO_7-Pad4)") (class "Default")
      (node (ref "U$3") (pin "4") (pinfunction "04_GPIO_7_4") (pintype "bidirectional"))
    )
    (net (code "83") (name "unconnected-(U$3-09_GPIO_6-Pad9)") (class "Default")
      (node (ref "U$3") (pin "9") (pinfunction "09_GPIO_6_9") (pintype "bidirectional"))
    )
    (net (code "84") (name "unconnected-(U$3-10_GPIO_5-Pad10)") (class "Default")
      (node (ref "U$3") (pin "10") (pinfunction "10_GPIO_5_10") (pintype "bidirectional"))
    )
    (net (code "85") (name "unconnected-(U$3-11_GPIO_4-Pad11)") (class "Default")
      (node (ref "U$3") (pin "11") (pinfunction "11_GPIO_4_11") (pintype "bidirectional"))
    )
    (net (code "86") (name "unconnected-(U$3-13_GPIO_2-Pad13)") (class "Default")
      (node (ref "U$3") (pin "13") (pinfunction "13_GPIO_2_13") (pintype "bidirectional"))
    )
    (net (code "87") (name "unconnected-(U$3-14_GPIO_1-Pad14)") (class "Default")
      (node (ref "U$3") (pin "14") (pinfunction "14_GPIO_1_14") (pintype "bidirectional"))
    )
    (net (code "88") (name "unconnected-(U1A-PA7-Pad32)") (class "Default")
      (node (ref "U1") (pin "32") (pinfunction "PA7_32") (pintype "bidirectional"))
    )
    (net (code "89") (name "unconnected-(U1A-PB0-Pad35)") (class "Default")
      (node (ref "U1") (pin "35") (pinfunction "PB0_35") (pintype "bidirectional"))
    )
    (net (code "90") (name "unconnected-(U1A-PB1-Pad36)") (class "Default")
      (node (ref "U1") (pin "36") (pinfunction "PB1_36") (pintype "bidirectional"))
    )
    (net (code "91") (name "unconnected-(U1A-PC0-Pad15)") (class "Default")
      (node (ref "U1") (pin "15") (pinfunction "PC0_15") (pintype "bidirectional"))
    )
    (net (code "92") (name "unconnected-(U1A-PC1-Pad16)") (class "Default")
      (node (ref "U1") (pin "16") (pinfunction "PC1_16") (pintype "bidirectional"))
    )
    (net (code "93") (name "unconnected-(U1A-PC4-Pad33)") (class "Default")
      (node (ref "U1") (pin "33") (pinfunction "PC4_33") (pintype "bidirectional"))
    )
    (net (code "94") (name "unconnected-(U1A-PC5-Pad34)") (class "Default")
      (node (ref "U1") (pin "34") (pinfunction "PC5_34") (pintype "bidirectional"))
    )
    (net (code "95") (name "unconnected-(U1A-PC15-Pad9)") (class "Default")
      (node (ref "U1") (pin "9") (pinfunction "PC15_9") (pintype "bidirectional"))
    )
    (net (code "96") (name "unconnected-(U1A-PE2-Pad1)") (class "Default")
      (node (ref "U1") (pin "1") (pinfunction "PE2_1") (pintype "bidirectional"))
    )
    (net (code "97") (name "unconnected-(U1A-PE3-Pad2)") (class "Default")
      (node (ref "U1") (pin "2") (pinfunction "PE3_2") (pintype "bidirectional"))
    )
    (net (code "98") (name "unconnected-(U1A-PE4-Pad3)") (class "Default")
      (node (ref "U1") (pin "3") (pinfunction "PE4_3") (pintype "bidirectional"))
    )
    (net (code "99") (name "unconnected-(U1A-PE5-Pad4)") (class "Default")
      (node (ref "U1") (pin "4") (pinfunction "PE5_4") (pintype "bidirectional"))
    )
    (net (code "100") (name "unconnected-(U1A-PE6-Pad5)") (class "Default")
      (node (ref "U1") (pin "5") (pinfunction "PE6_5") (pintype "bidirectional"))
    )
    (net (code "101") (name "unconnected-(U1A-PE7-Pad38)") (class "Default")
      (node (ref "U1") (pin "38") (pinfunction "PE7_38") (pintype "bidirectional"))
    )
    (net (code "102") (name "unconnected-(U1A-PE10-Pad41)") (class "Default")
      (node (ref "U1") (pin "41") (pinfunction "PE10_41") (pintype "bidirectional"))
    )
    (net (code "103") (name "unconnected-(U1A-PE12-Pad43)") (class "Default")
      (node (ref "U1") (pin "43") (pinfunction "PE12_43") (pintype "bidirectional"))
    )
    (net (code "104") (name "unconnected-(U1A-PE15-Pad46)") (class "Default")
      (node (ref "U1") (pin "46") (pinfunction "PE15_46") (pintype "bidirectional"))
    )
    (net (code "105") (name "unconnected-(U1B-PA12-Pad71)") (class "Default")
      (node (ref "U1") (pin "71") (pinfunction "PA12_71") (pintype "bidirectional"))
    )
    (net (code "106") (name "unconnected-(U1B-PA15-Pad77)") (class "Default")
      (node (ref "U1") (pin "77") (pinfunction "PA15_77") (pintype "bidirectional"))
    )
    (net (code "107") (name "unconnected-(U1B-PA_11-Pad70)") (class "Default")
      (node (ref "U1") (pin "70") (pinfunction "PA_11_70") (pintype "bidirectional"))
    )
    (net (code "108") (name "unconnected-(U1B-PB12-Pad51)") (class "Default")
      (node (ref "U1") (pin "51") (pinfunction "PB12_51") (pintype "bidirectional"))
    )
    (net (code "109") (name "unconnected-(U1B-PC8-Pad65)") (class "Default")
      (node (ref "U1") (pin "65") (pinfunction "PC8_65") (pintype "bidirectional"))
    )
    (net (code "110") (name "unconnected-(U1B-PD2-Pad83)") (class "Default")
      (node (ref "U1") (pin "83") (pinfunction "PD2_83") (pintype "bidirectional"))
    )
    (net (code "111") (name "unconnected-(U1B-PD3-Pad84)") (class "Default")
      (node (ref "U1") (pin "84") (pinfunction "PD3_84") (pintype "bidirectional"))
    )
    (net (code "112") (name "unconnected-(U1B-PD4-Pad85)") (class "Default")
      (node (ref "U1") (pin "85") (pinfunction "PD4_85") (pintype "bidirectional"))
    )
    (net (code "113") (name "unconnected-(U1B-PD7-Pad88)") (class "Default")
      (node (ref "U1") (pin "88") (pinfunction "PD7_88") (pintype "bidirectional"))
    )
    (net (code "114") (name "unconnected-(U1B-PD10-Pad57)") (class "Default")
      (node (ref "U1") (pin "57") (pinfunction "PD10_57") (pintype "bidirectional"))
    )
    (net (code "115") (name "unconnected-(U2-EN-Pad4)") (class "Default")
      (node (ref "U2") (pin "4") (pinfunction "EN_4") (pintype "bidirectional"))
    )
  )
)
